# tang2.net
KiCad netlist of a schematic drawn in Altium Designer
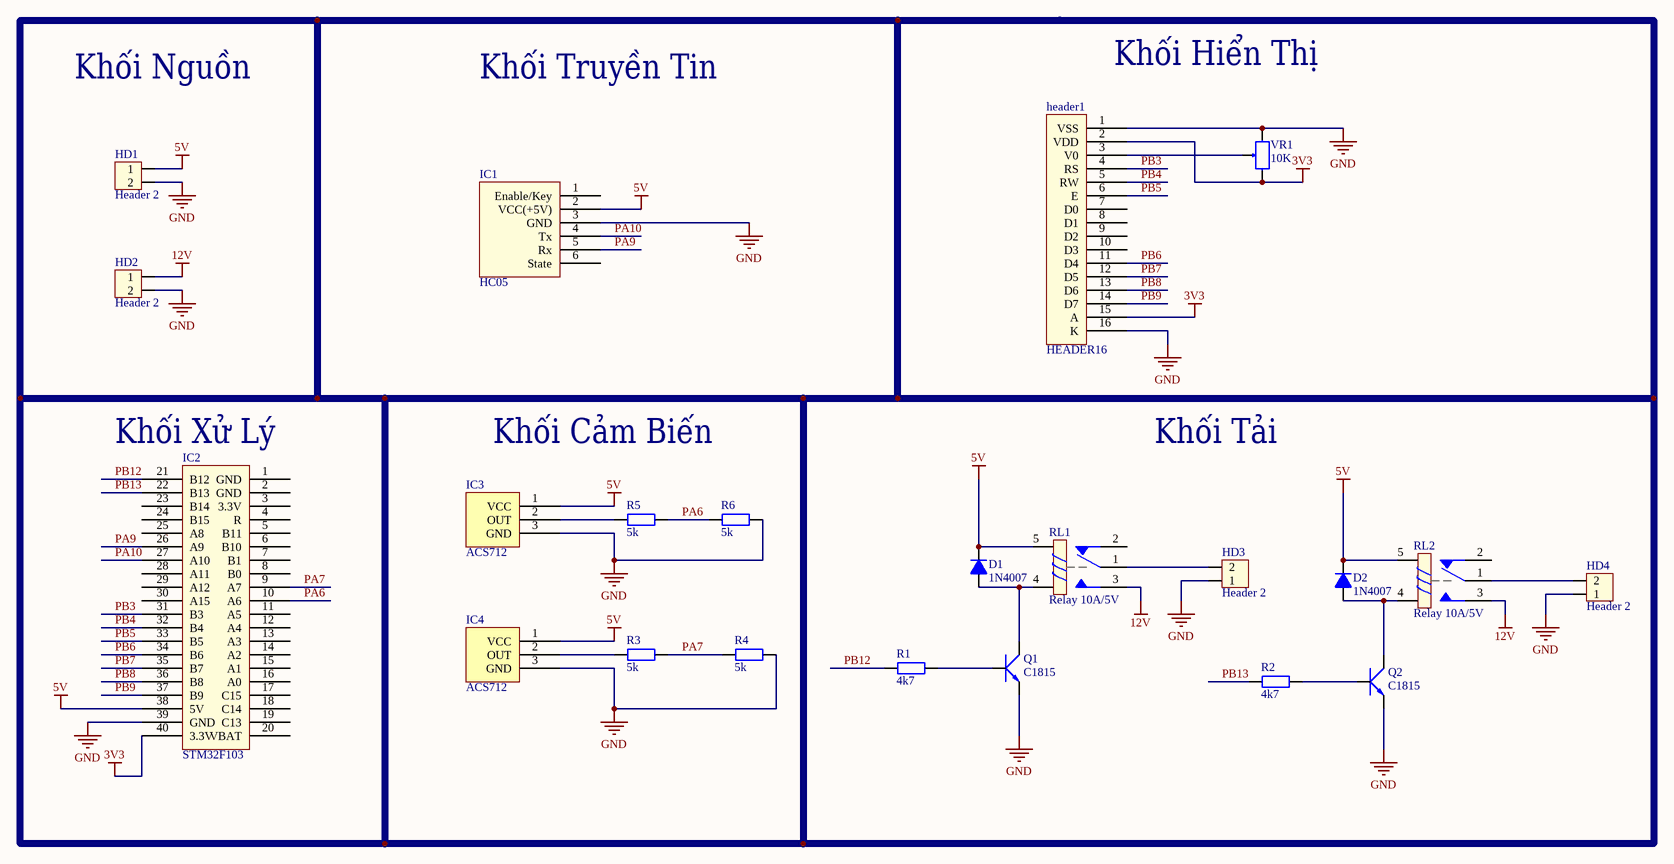
[diagram p0: tang2.SchDoc]

(export (version "E")
  (design (tool "Eeschema 10.0.6"))
  (components
    (comp (ref "D1")
      (value "1N4007")
      (footprint "D1A")
      (description "Diode 1A")
      (libsource (lib "syhaunguyen") (part "D1A"))
    )
    (comp (ref "D2")
      (value "1N4007")
      (footprint "D1A")
      (description "Diode 1A")
      (libsource (lib "syhaunguyen") (part "D1A"))
    )
    (comp (ref "HD1")
      (value "Header 2")
      (footprint "HED2")
      (description "Header 2 (Green)")
      (libsource (lib "syhaunguyen") (part "Hed2"))
    )
    (comp (ref "HD2")
      (value "Header 2")
      (footprint "HED2")
      (description "Header 2 (Green)")
      (libsource (lib "syhaunguyen") (part "Hed2"))
    )
    (comp (ref "HD3")
      (value "Header 2")
      (footprint "HED2")
      (description "Header 2 (Green)")
      (libsource (lib "") (part "Hed2_1"))
    )
    (comp (ref "HD4")
      (value "Header 2")
      (footprint "HED2")
      (description "Header 2 (Green)")
      (libsource (lib "") (part "Hed2_1"))
    )
    (comp (ref "header1")
      (value "HEADER16")
      (footprint "header16_pin")
      (libsource (lib "header16") (part "HEADER16"))
    )
    (comp (ref "IC1") (value "HC05") (footprint "HC05_Pin") (libsource (lib "hc05") (part "HC05")))
    (comp (ref "IC2")
      (value "STM32F103")
      (footprint "STM32")
      (libsource (lib "STM32F103") (part "STM32F103"))
    )
    (comp (ref "IC3")
      (value "ACS712")
      (footprint "ACS712:PCBComponent_1")
      (libsource (lib "ACS712") (part "ACS712"))
    )
    (comp (ref "IC4")
      (value "ACS712")
      (footprint "ACS712:PCBComponent_1")
      (libsource (lib "ACS712") (part "ACS712"))
    )
    (comp (ref "Q1")
      (value "C1815")
      (footprint "QTO-92")
      (description "NPN 600mW, ECB")
      (libsource (lib "syhaunguyen") (part "C1815"))
    )
    (comp (ref "Q2")
      (value "C1815")
      (footprint "QTO-92")
      (description "NPN 600mW, ECB")
      (libsource (lib "syhaunguyen") (part "C1815"))
    )
    (comp (ref "R1")
      (value "4k7")
      (footprint "R1/4W")
      (description "Resistor 1/4W")
      (libsource (lib "syhaunguyen") (part "R1/4W"))
    )
    (comp (ref "R2")
      (value "4k7")
      (footprint "R1/4W")
      (description "Resistor 1/4W")
      (libsource (lib "syhaunguyen") (part "R1/4W"))
    )
    (comp (ref "R3")
      (value "5k")
      (footprint "R1/4W")
      (description "Resistor 1/4W")
      (libsource (lib "syhaunguyen") (part "R1/4W"))
    )
    (comp (ref "R4")
      (value "5k")
      (footprint "R1/4W")
      (description "Resistor 1/4W")
      (libsource (lib "syhaunguyen") (part "R1/4W"))
    )
    (comp (ref "R5")
      (value "5k")
      (footprint "R1/4W")
      (description "Resistor 1/4W")
      (libsource (lib "syhaunguyen") (part "R1/4W"))
    )
    (comp (ref "R6")
      (value "5k")
      (footprint "R1/4W")
      (description "Resistor 1/4W")
      (libsource (lib "syhaunguyen") (part "R1/4W"))
    )
    (comp (ref "RL1")
      (value "Relay 10A/5V")
      (footprint "RL_SPDT_10A")
      (description "Relay SPDT,10A - 12VDC 5 Pin")
      (libsource (lib "syhaunguyen") (part "Relay 1"))
    )
    (comp (ref "RL2")
      (value "Relay 10A/5V")
      (footprint "RL_SPDT_10A")
      (description "Relay SPDT,10A - 12VDC 5 Pin")
      (libsource (lib "syhaunguyen") (part "Relay 1"))
    )
    (comp (ref "VR1")
      (value "10K")
      (footprint "VR")
      (description "Var Resistor")
      (libsource (lib "syhaunguyen") (part "VR"))
    )
  )
  (nets
    (net (code "1") (name "/PA6") (class "Default")
      (node (ref "IC2") (pin "10") (pinfunction "A6_10") (pintype "passive"))
      (node (ref "R5") (pin "2") (pinfunction "2_2") (pintype "passive"))
      (node (ref "R6") (pin "1") (pinfunction "1_1") (pintype "passive"))
    )
    (net (code "2") (name "/PA7") (class "Default")
      (node (ref "IC2") (pin "9") (pinfunction "A7_9") (pintype "passive"))
      (node (ref "R3") (pin "2") (pinfunction "2_2") (pintype "passive"))
      (node (ref "R4") (pin "1") (pinfunction "1_1") (pintype "passive"))
    )
    (net (code "3") (name "/PA9") (class "Default")
      (node (ref "IC1") (pin "5") (pinfunction "Rx_5") (pintype "passive"))
      (node (ref "IC2") (pin "26") (pinfunction "A9_26") (pintype "passive"))
    )
    (net (code "4") (name "/PA10") (class "Default")
      (node (ref "IC1") (pin "4") (pinfunction "Tx_4") (pintype "passive"))
      (node (ref "IC2") (pin "27") (pinfunction "A10_27") (pintype "passive"))
    )
    (net (code "5") (name "/PB3") (class "Default")
      (node (ref "IC2") (pin "31") (pinfunction "B3_31") (pintype "passive"))
      (node (ref "header1") (pin "4") (pinfunction "RS_4") (pintype "passive"))
    )
    (net (code "6") (name "/PB4") (class "Default")
      (node (ref "IC2") (pin "32") (pinfunction "B4_32") (pintype "passive"))
      (node (ref "header1") (pin "5") (pinfunction "RW_5") (pintype "passive"))
    )
    (net (code "7") (name "/PB5") (class "Default")
      (node (ref "IC2") (pin "33") (pinfunction "B5_33") (pintype "passive"))
      (node (ref "header1") (pin "6") (pinfunction "E_6") (pintype "passive"))
    )
    (net (code "8") (name "/PB6") (class "Default")
      (node (ref "IC2") (pin "34") (pinfunction "B6_34") (pintype "passive"))
      (node (ref "header1") (pin "11") (pinfunction "D4_11") (pintype "passive"))
    )
    (net (code "9") (name "/PB7") (class "Default")
      (node (ref "IC2") (pin "35") (pinfunction "B7_35") (pintype "passive"))
      (node (ref "header1") (pin "12") (pinfunction "D5_12") (pintype "passive"))
    )
    (net (code "10") (name "/PB8") (class "Default")
      (node (ref "IC2") (pin "36") (pinfunction "B8_36") (pintype "passive"))
      (node (ref "header1") (pin "13") (pinfunction "D6_13") (pintype "passive"))
    )
    (net (code "11") (name "/PB9") (class "Default")
      (node (ref "IC2") (pin "37") (pinfunction "B9_37") (pintype "passive"))
      (node (ref "header1") (pin "14") (pinfunction "D7_14") (pintype "passive"))
    )
    (net (code "12") (name "/PB12") (class "Default")
      (node (ref "IC2") (pin "21") (pinfunction "B12_21") (pintype "passive"))
      (node (ref "R1") (pin "1") (pinfunction "1_1") (pintype "passive"))
    )
    (net (code "13") (name "/PB13") (class "Default")
      (node (ref "IC2") (pin "22") (pinfunction "B13_22") (pintype "passive"))
      (node (ref "R2") (pin "1") (pinfunction "1_1") (pintype "passive"))
    )
    (net (code "14") (name "3V3") (class "Default")
      (node (ref "IC2") (pin "40") (pinfunction "3.3V_40") (pintype "passive"))
      (node (ref "VR1") (pin "1") (pinfunction "1_1") (pintype "passive"))
      (node (ref "header1") (pin "15") (pinfunction "A_15") (pintype "passive"))
      (node (ref "header1") (pin "2") (pinfunction "VDD_2") (pintype "passive"))
    )
    (net (code "15") (name "5V") (class "Default")
      (node (ref "D1") (pin "2") (pinfunction "K_2") (pintype "passive"))
      (node (ref "D2") (pin "2") (pinfunction "K_2") (pintype "passive"))
      (node (ref "HD1") (pin "1") (pinfunction "1_1") (pintype "passive"))
      (node (ref "IC1") (pin "2") (pinfunction "VCC(+5V)_2") (pintype "passive"))
      (node (ref "IC2") (pin "38") (pinfunction "5V_38") (pintype "passive"))
      (node (ref "IC3") (pin "1") (pinfunction "VCC_1") (pintype "passive"))
      (node (ref "IC4") (pin "1") (pinfunction "VCC_1") (pintype "passive"))
      (node (ref "RL1") (pin "5") (pinfunction "5_5") (pintype "passive"))
      (node (ref "RL2") (pin "5") (pinfunction "5_5") (pintype "passive"))
    )
    (net (code "16") (name "12V") (class "Default")
      (node (ref "HD2") (pin "1") (pinfunction "1_1") (pintype "passive"))
      (node (ref "RL1") (pin "3") (pinfunction "3_3") (pintype "passive"))
      (node (ref "RL2") (pin "3") (pinfunction "3_3") (pintype "passive"))
    )
    (net (code "17") (name "GND") (class "Default")
      (node (ref "HD1") (pin "2") (pinfunction "2_2") (pintype "passive"))
      (node (ref "HD2") (pin "2") (pinfunction "2_2") (pintype "passive"))
      (node (ref "HD3") (pin "1") (pinfunction "1_1") (pintype "passive"))
      (node (ref "HD4") (pin "1") (pinfunction "1_1") (pintype "passive"))
      (node (ref "IC1") (pin "3") (pinfunction "GND_3") (pintype "passive"))
      (node (ref "IC2") (pin "39") (pinfunction "GND_39") (pintype "passive"))
      (node (ref "IC3") (pin "3") (pinfunction "GND_3") (pintype "passive"))
      (node (ref "IC4") (pin "3") (pinfunction "GND_3") (pintype "passive"))
      (node (ref "Q1") (pin "1") (pinfunction "E_1") (pintype "passive"))
      (node (ref "Q2") (pin "1") (pinfunction "E_1") (pintype "passive"))
      (node (ref "R4") (pin "2") (pinfunction "2_2") (pintype "passive"))
      (node (ref "R6") (pin "2") (pinfunction "2_2") (pintype "passive"))
      (node (ref "VR1") (pin "3") (pinfunction "3_3") (pintype "passive"))
      (node (ref "header1") (pin "1") (pinfunction "VSS_1") (pintype "passive"))
      (node (ref "header1") (pin "16") (pinfunction "K_16") (pintype "passive"))
    )
    (net (code "18") (name "Net-(D1-A)") (class "Default")
      (node (ref "D1") (pin "1") (pinfunction "A_1") (pintype "passive"))
      (node (ref "Q1") (pin "2") (pinfunction "C_2") (pintype "passive"))
      (node (ref "RL1") (pin "4") (pinfunction "4_4") (pintype "passive"))
    )
    (net (code "19") (name "Net-(D2-A)") (class "Default")
      (node (ref "D2") (pin "1") (pinfunction "A_1") (pintype "passive"))
      (node (ref "Q2") (pin "2") (pinfunction "C_2") (pintype "passive"))
      (node (ref "RL2") (pin "4") (pinfunction "4_4") (pintype "passive"))
    )
    (net (code "20") (name "Net-(HD3-Pad2)") (class "Default")
      (node (ref "HD3") (pin "2") (pinfunction "2_2") (pintype "passive"))
      (node (ref "RL1") (pin "1") (pinfunction "1_1") (pintype "passive"))
    )
    (net (code "21") (name "Net-(HD4-Pad2)") (class "Default")
      (node (ref "HD4") (pin "2") (pinfunction "2_2") (pintype "passive"))
      (node (ref "RL2") (pin "1") (pinfunction "1_1") (pintype "passive"))
    )
    (net (code "22") (name "Net-(IC3-OUT)") (class "Default")
      (node (ref "IC3") (pin "2") (pinfunction "OUT_2") (pintype "passive"))
      (node (ref "R5") (pin "1") (pinfunction "1_1") (pintype "passive"))
    )
    (net (code "23") (name "Net-(IC4-OUT)") (class "Default")
      (node (ref "IC4") (pin "2") (pinfunction "OUT_2") (pintype "passive"))
      (node (ref "R3") (pin "1") (pinfunction "1_1") (pintype "passive"))
    )
    (net (code "24") (name "Net-(Q1-B)") (class "Default")
      (node (ref "Q1") (pin "3") (pinfunction "B_3") (pintype "passive"))
      (node (ref "R1") (pin "2") (pinfunction "2_2") (pintype "passive"))
    )
    (net (code "25") (name "Net-(Q2-B)") (class "Default")
      (node (ref "Q2") (pin "3") (pinfunction "B_3") (pintype "passive"))
      (node (ref "R2") (pin "2") (pinfunction "2_2") (pintype "passive"))
    )
    (net (code "26") (name "Net-(header1-V0)") (class "Default")
      (node (ref "VR1") (pin "2") (pinfunction "2_2") (pintype "passive"))
      (node (ref "header1") (pin "3") (pinfunction "V0_3") (pintype "passive"))
    )
    (net (code "27") (name "unconnected-(IC1-Enable{slash}Key-Pad1)") (class "Default")
      (node (ref "IC1") (pin "1") (pinfunction "Enable/Key_1") (pintype "passive"))
    )
    (net (code "28") (name "unconnected-(IC1-State-Pad6)") (class "Default")
      (node (ref "IC1") (pin "6") (pinfunction "State_6") (pintype "passive"))
    )
    (net (code "29") (name "unconnected-(IC2-3.3V-Pad3)") (class "Default")
      (node (ref "IC2") (pin "3") (pinfunction "3.3V_3") (pintype "passive"))
    )
    (net (code "30") (name "unconnected-(IC2-A0-Pad16)") (class "Default")
      (node (ref "IC2") (pin "16") (pinfunction "A0_16") (pintype "passive"))
    )
    (net (code "31") (name "unconnected-(IC2-A1-Pad15)") (class "Default")
      (node (ref "IC2") (pin "15") (pinfunction "A1_15") (pintype "passive"))
    )
    (net (code "32") (name "unconnected-(IC2-A2-Pad14)") (class "Default")
      (node (ref "IC2") (pin "14") (pinfunction "A2_14") (pintype "passive"))
    )
    (net (code "33") (name "unconnected-(IC2-A3-Pad13)") (class "Default")
      (node (ref "IC2") (pin "13") (pinfunction "A3_13") (pintype "passive"))
    )
    (net (code "34") (name "unconnected-(IC2-A4-Pad12)") (class "Default")
      (node (ref "IC2") (pin "12") (pinfunction "A4_12") (pintype "passive"))
    )
    (net (code "35") (name "unconnected-(IC2-A5-Pad11)") (class "Default")
      (node (ref "IC2") (pin "11") (pinfunction "A5_11") (pintype "passive"))
    )
    (net (code "36") (name "unconnected-(IC2-A8-Pad25)") (class "Default")
      (node (ref "IC2") (pin "25") (pinfunction "A8_25") (pintype "passive"))
    )
    (net (code "37") (name "unconnected-(IC2-A11-Pad28)") (class "Default")
      (node (ref "IC2") (pin "28") (pinfunction "A11_28") (pintype "passive"))
    )
    (net (code "38") (name "unconnected-(IC2-A12-Pad29)") (class "Default")
      (node (ref "IC2") (pin "29") (pinfunction "A12_29") (pintype "passive"))
    )
    (net (code "39") (name "unconnected-(IC2-A15-Pad30)") (class "Default")
      (node (ref "IC2") (pin "30") (pinfunction "A15_30") (pintype "passive"))
    )
    (net (code "40") (name "unconnected-(IC2-B0-Pad8)") (class "Default")
      (node (ref "IC2") (pin "8") (pinfunction "B0_8") (pintype "passive"))
    )
    (net (code "41") (name "unconnected-(IC2-B1-Pad7)") (class "Default")
      (node (ref "IC2") (pin "7") (pinfunction "B1_7") (pintype "passive"))
    )
    (net (code "42") (name "unconnected-(IC2-B10-Pad6)") (class "Default")
      (node (ref "IC2") (pin "6") (pinfunction "B10_6") (pintype "passive"))
    )
    (net (code "43") (name "unconnected-(IC2-B11-Pad5)") (class "Default")
      (node (ref "IC2") (pin "5") (pinfunction "B11_5") (pintype "passive"))
    )
    (net (code "44") (name "unconnected-(IC2-B14-Pad23)") (class "Default")
      (node (ref "IC2") (pin "23") (pinfunction "B14_23") (pintype "passive"))
    )
    (net (code "45") (name "unconnected-(IC2-B15-Pad24)") (class "Default")
      (node (ref "IC2") (pin "24") (pinfunction "B15_24") (pintype "passive"))
    )
    (net (code "46") (name "unconnected-(IC2-C13-Pad19)") (class "Default")
      (node (ref "IC2") (pin "19") (pinfunction "C13_19") (pintype "passive"))
    )
    (net (code "47") (name "unconnected-(IC2-C14-Pad18)") (class "Default")
      (node (ref "IC2") (pin "18") (pinfunction "C14_18") (pintype "passive"))
    )
    (net (code "48") (name "unconnected-(IC2-C15-Pad17)") (class "Default")
      (node (ref "IC2") (pin "17") (pinfunction "C15_17") (pintype "passive"))
    )
    (net (code "49") (name "unconnected-(IC2-GND-Pad1)") (class "Default")
      (node (ref "IC2") (pin "1") (pinfunction "GND_1") (pintype "passive"))
    )
    (net (code "50") (name "unconnected-(IC2-GND-Pad2)") (class "Default")
      (node (ref "IC2") (pin "2") (pinfunction "GND_2") (pintype "passive"))
    )
    (net (code "51") (name "unconnected-(IC2-R-Pad4)") (class "Default")
      (node (ref "IC2") (pin "4") (pinfunction "R_4") (pintype "passive"))
    )
    (net (code "52") (name "unconnected-(IC2-VBAT-Pad20)") (class "Default")
      (node (ref "IC2") (pin "20") (pinfunction "VBAT_20") (pintype "passive"))
    )
    (net (code "53") (name "unconnected-(RL1-Pad2)") (class "Default")
      (node (ref "RL1") (pin "2") (pinfunction "2_2") (pintype "passive"))
    )
    (net (code "54") (name "unconnected-(RL2-Pad2)") (class "Default")
      (node (ref "RL2") (pin "2") (pinfunction "2_2") (pintype "passive"))
    )
    (net (code "55") (name "unconnected-(header1-D0-Pad7)") (class "Default")
      (node (ref "header1") (pin "7") (pinfunction "D0_7") (pintype "passive"))
    )
    (net (code "56") (name "unconnected-(header1-D1-Pad8)") (class "Default")
      (node (ref "header1") (pin "8") (pinfunction "D1_8") (pintype "passive"))
    )
    (net (code "57") (name "unconnected-(header1-D2-Pad9)") (class "Default")
      (node (ref "header1") (pin "9") (pinfunction "D2_9") (pintype "passive"))
    )
    (net (code "58") (name "unconnected-(header1-D3-Pad10)") (class "Default")
      (node (ref "header1") (pin "10") (pinfunction "D3_10") (pintype "passive"))
    )
  )
)
